# Si7020-BreakBoard.net
KiCad netlist of a schematic drawn in EAGLE
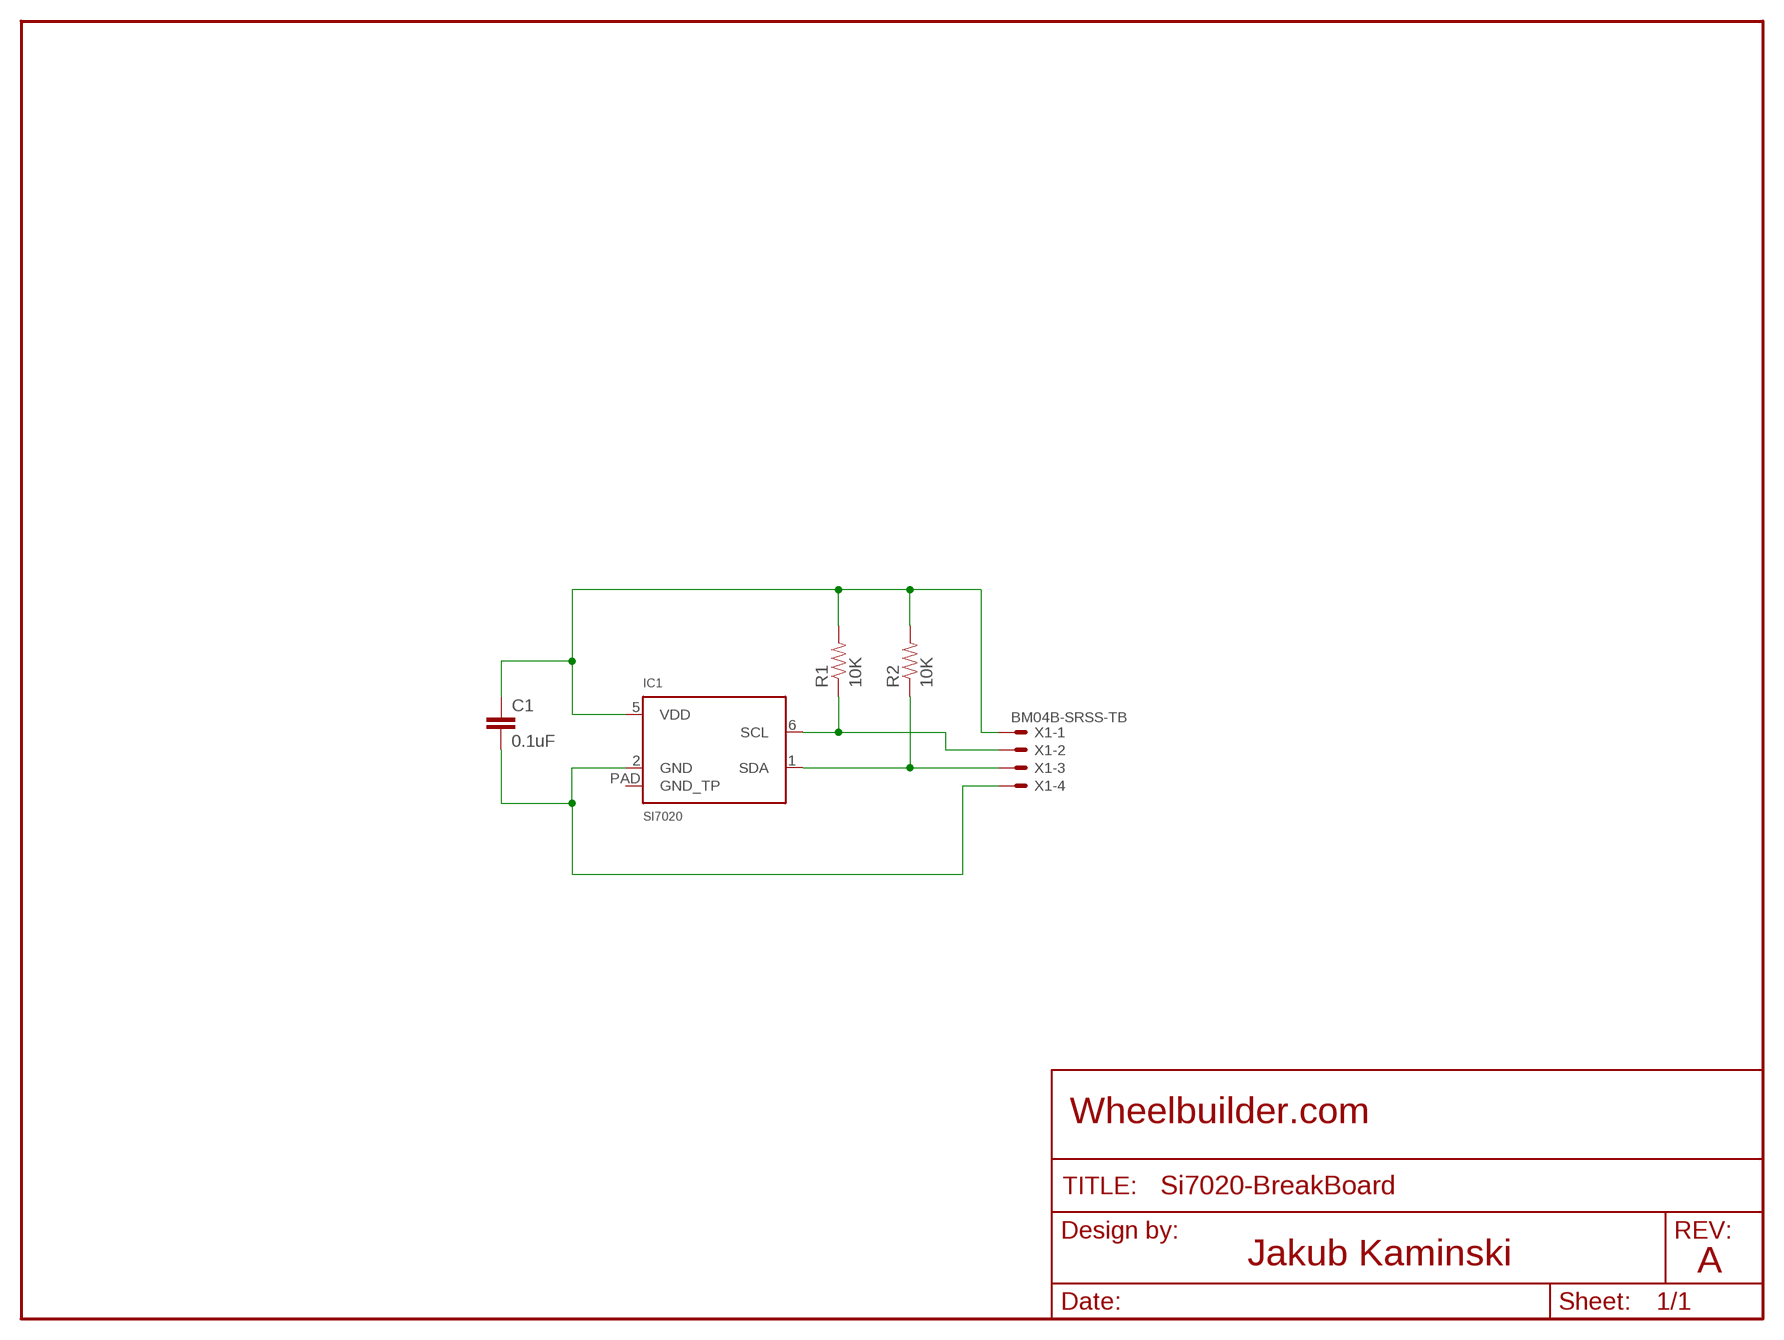
[diagram p0: schematic, sheet 1]

(export (version "E")
  (design (tool "Eeschema 10.0.6"))
  (components
    (comp (ref "C1")
      (value "0.1uF")
      (footprint "eagle-import:0603-CAP")
      (libsource (lib "eagle-import") (part "0.1UF-25V(+80/-20%)(0603)"))
    )
    (comp (ref "FRAME1")
      (value "FRAME-LETTER")
      (footprint "eagle-import:CREATIVE_COMMONS")
      (libsource (lib "eagle-import") (part "FRAME-LETTER"))
    )
    (comp (ref "IC1")
      (value "SI7020")
      (footprint "eagle-import:DFN6-3X3")
      (libsource (lib "eagle-import") (part "SI7020"))
    )
    (comp (ref "R1")
      (value "10K")
      (footprint "eagle-import:0603-RES")
      (libsource (lib "eagle-import") (part "10KOHM1/10W1%(0603)0603"))
    )
    (comp (ref "R2")
      (value "10K")
      (footprint "eagle-import:0603-RES")
      (libsource (lib "eagle-import") (part "10KOHM1/10W1%(0603)0603"))
    )
    (comp (ref "X1")
      (value "BM04B-SRSS-TB")
      (footprint "eagle-import:BM04B-SRSS-TB")
      (libsource (lib "eagle-import") (part "?M04B-SRSS-TBB"))
    )
  )
  (nets
    (net (code "1") (name "Net-(IC1-GND)") (class "Default")
      (node (ref "C1") (pin "2") (pinfunction "2_2") (pintype "passive"))
      (node (ref "IC1") (pin "2") (pinfunction "GND_2") (pintype "bidirectional"))
      (node (ref "X1") (pin "4") (pinfunction "S_4") (pintype "passive"))
    )
    (net (code "2") (name "Net-(IC1-SCL)") (class "Default")
      (node (ref "IC1") (pin "6") (pinfunction "SCL_6") (pintype "bidirectional"))
      (node (ref "R1") (pin "1") (pinfunction "1_1") (pintype "passive"))
      (node (ref "X1") (pin "2") (pinfunction "S_2") (pintype "passive"))
    )
    (net (code "3") (name "Net-(IC1-SDA)") (class "Default")
      (node (ref "IC1") (pin "1") (pinfunction "SDA_1") (pintype "bidirectional"))
      (node (ref "R2") (pin "1") (pinfunction "1_1") (pintype "passive"))
      (node (ref "X1") (pin "3") (pinfunction "S_3") (pintype "passive"))
    )
    (net (code "4") (name "Net-(IC1-VDD)") (class "Default")
      (node (ref "C1") (pin "1") (pinfunction "1_1") (pintype "passive"))
      (node (ref "IC1") (pin "5") (pinfunction "VDD_5") (pintype "bidirectional"))
      (node (ref "R1") (pin "2") (pinfunction "2_2") (pintype "passive"))
      (node (ref "R2") (pin "2") (pinfunction "2_2") (pintype "passive"))
      (node (ref "X1") (pin "1") (pinfunction "S_1") (pintype "passive"))
    )
    (net (code "5") (name "unconnected-(IC1-GND_TP-PadPAD)") (class "Default")
      (node (ref "IC1") (pin "PAD") (pinfunction "GND_TP_PAD") (pintype "bidirectional"))
    )
  )
)
